# Scarab.net
KiCad netlist of a schematic drawn in EAGLE
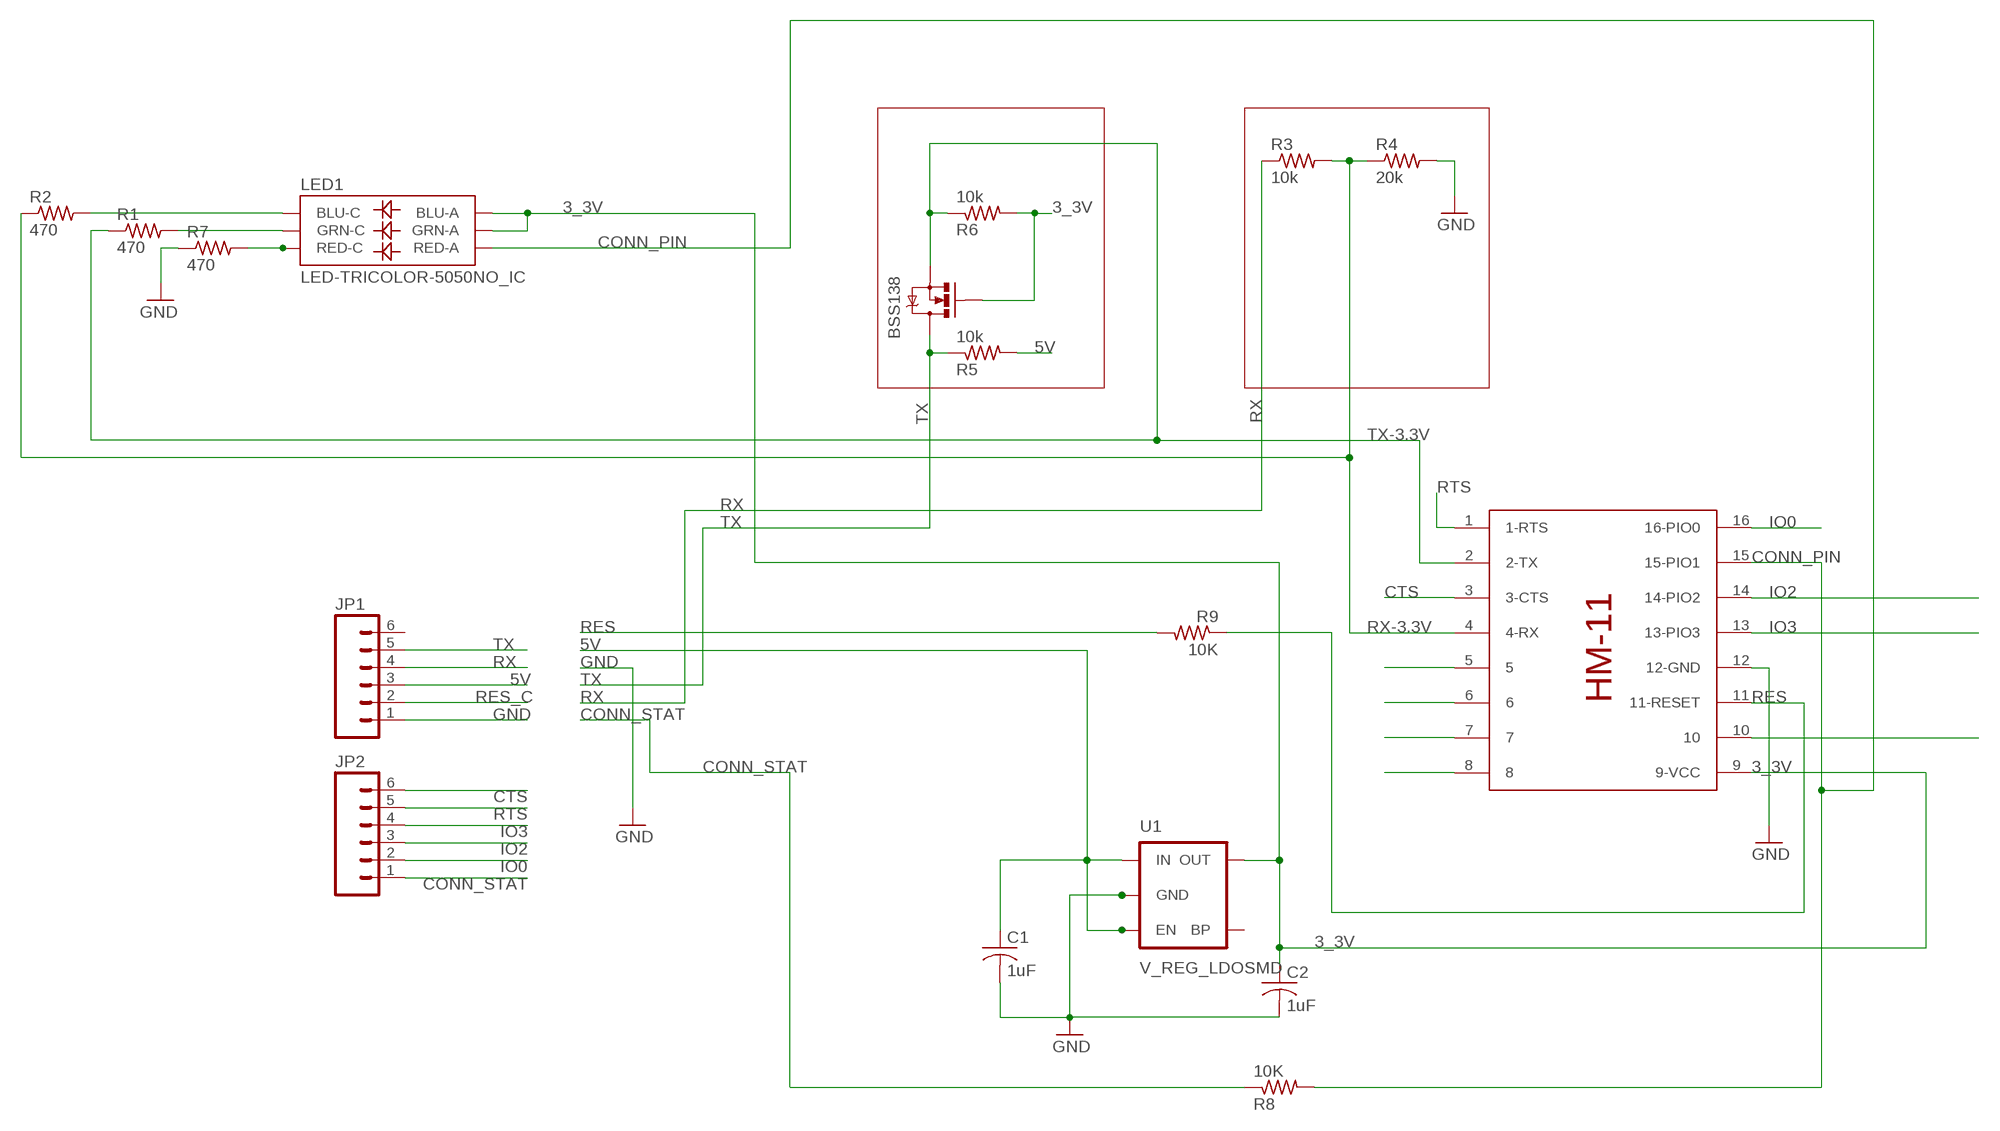
[diagram p0: schematic, sheet 1]

(export (version "E")
  (design (tool "Eeschema 10.0.6"))
  (components
    (comp (ref "BSS138")
      (value "MOSFET-NCHANNELSMD")
      (footprint "eagle-import:SOT23-3")
      (libsource (lib "eagle-import") (part "MOSFET-NCHANNELSMD"))
    )
    (comp (ref "C1")
      (value "1uF")
      (footprint "eagle-import:C0402")
      (libsource (lib "eagle-import") (part "C-USC0402"))
    )
    (comp (ref "C2")
      (value "1uF")
      (footprint "eagle-import:C0402")
      (libsource (lib "eagle-import") (part "C-USC0402"))
    )
    (comp (ref "JP1")
      (value "M06LOCK")
      (footprint "eagle-import:1X06_LOCK")
      (libsource (lib "eagle-import") (part "M06LOCK"))
    )
    (comp (ref "JP2")
      (value "M06LOCK")
      (footprint "eagle-import:1X06_LOCK")
      (libsource (lib "eagle-import") (part "M06LOCK"))
    )
    (comp (ref "LED1")
      (value "LED-TRICOLOR-5050NO_IC")
      (footprint "eagle-import:LED-TRICOLOR-5050")
      (libsource (lib "eagle-import") (part "LED-TRICOLOR-5050NO_IC"))
    )
    (comp (ref "R1")
      (value "470")
      (footprint "eagle-import:R0402")
      (libsource (lib "eagle-import") (part "R-US_R0402"))
    )
    (comp (ref "R2")
      (value "470")
      (footprint "eagle-import:R0402")
      (libsource (lib "eagle-import") (part "R-US_R0402"))
    )
    (comp (ref "R3")
      (value "10k")
      (footprint "eagle-import:R0402")
      (libsource (lib "eagle-import") (part "R-US_R0402"))
    )
    (comp (ref "R4")
      (value "20k")
      (footprint "eagle-import:R0402")
      (libsource (lib "eagle-import") (part "R-US_R0402"))
    )
    (comp (ref "R5")
      (value "10k")
      (footprint "eagle-import:R0402")
      (libsource (lib "eagle-import") (part "R-US_R0402"))
    )
    (comp (ref "R6")
      (value "10k")
      (footprint "eagle-import:R0402")
      (libsource (lib "eagle-import") (part "R-US_R0402"))
    )
    (comp (ref "R7")
      (value "470")
      (footprint "eagle-import:R0402")
      (libsource (lib "eagle-import") (part "R-US_R0402"))
    )
    (comp (ref "R8")
      (value "10K")
      (footprint "eagle-import:R0402")
      (libsource (lib "eagle-import") (part "R-US_R0402"))
    )
    (comp (ref "R9")
      (value "10K")
      (footprint "eagle-import:R0402")
      (libsource (lib "eagle-import") (part "R-US_R0402"))
    )
    (comp (ref "U$1")
      (value "HM-11")
      (footprint "eagle-import:HM-11")
      (libsource (lib "eagle-import") (part "HM-11"))
    )
    (comp (ref "U1")
      (value "V_REG_LDOSMD")
      (footprint "eagle-import:SOT23-5")
      (libsource (lib "eagle-import") (part "V_REG_LDOSMD"))
    )
  )
  (nets
    (net (code "1") (name "/3_3V") (class "Default")
      (node (ref "BSS138") (pin "1") (pinfunction "G_1") (pintype "passive"))
      (node (ref "C2") (pin "1") (pinfunction "1_1") (pintype "passive"))
      (node (ref "LED1") (pin "1") (pinfunction "GRN-A_1") (pintype "bidirectional"))
      (node (ref "LED1") (pin "3") (pinfunction "BLU-A_3") (pintype "bidirectional"))
      (node (ref "R6") (pin "2") (pinfunction "2_2") (pintype "passive"))
      (node (ref "U$1") (pin "9") (pinfunction "9-VCC_9") (pintype "bidirectional"))
      (node (ref "U1") (pin "5") (pinfunction "OUT_5") (pintype "passive"))
    )
    (net (code "2") (name "/5V") (class "Default")
      (node (ref "C1") (pin "1") (pinfunction "1_1") (pintype "passive"))
      (node (ref "JP1") (pin "3") (pinfunction "3_3") (pintype "passive"))
      (node (ref "R5") (pin "2") (pinfunction "2_2") (pintype "passive"))
      (node (ref "U1") (pin "1") (pinfunction "IN_1") (pintype "input"))
      (node (ref "U1") (pin "3") (pinfunction "EN_3") (pintype "input"))
    )
    (net (code "3") (name "/CONN_PIN") (class "Default")
      (node (ref "LED1") (pin "2") (pinfunction "RED-A_2") (pintype "bidirectional"))
      (node (ref "R8") (pin "2") (pinfunction "2_2") (pintype "passive"))
      (node (ref "U$1") (pin "15") (pinfunction "15-PIO1_15") (pintype "bidirectional"))
    )
    (net (code "4") (name "/CONN_STAT") (class "Default")
      (node (ref "JP2") (pin "1") (pinfunction "1_1") (pintype "passive"))
      (node (ref "R8") (pin "1") (pinfunction "1_1") (pintype "passive"))
    )
    (net (code "5") (name "/CTS") (class "Default")
      (node (ref "JP2") (pin "6") (pinfunction "6_6") (pintype "passive"))
      (node (ref "U$1") (pin "3") (pinfunction "3-CTS_3") (pintype "bidirectional"))
    )
    (net (code "6") (name "/IO0") (class "Default")
      (node (ref "JP2") (pin "2") (pinfunction "2_2") (pintype "passive"))
      (node (ref "U$1") (pin "16") (pinfunction "16-PIO0_16") (pintype "bidirectional"))
    )
    (net (code "7") (name "/IO2") (class "Default")
      (node (ref "JP2") (pin "3") (pinfunction "3_3") (pintype "passive"))
      (node (ref "U$1") (pin "14") (pinfunction "14-PIO2_14") (pintype "bidirectional"))
    )
    (net (code "8") (name "/IO3") (class "Default")
      (node (ref "JP2") (pin "4") (pinfunction "4_4") (pintype "passive"))
      (node (ref "U$1") (pin "13") (pinfunction "13-PIO3_13") (pintype "bidirectional"))
    )
    (net (code "9") (name "/RES") (class "Default")
      (node (ref "R9") (pin "1") (pinfunction "1_1") (pintype "passive"))
      (node (ref "U$1") (pin "11") (pinfunction "11-RESET_11") (pintype "bidirectional"))
    )
    (net (code "10") (name "/RES_C") (class "Default")
      (node (ref "JP1") (pin "2") (pinfunction "2_2") (pintype "passive"))
      (node (ref "R9") (pin "2") (pinfunction "2_2") (pintype "passive"))
    )
    (net (code "11") (name "/RTS") (class "Default")
      (node (ref "JP2") (pin "5") (pinfunction "5_5") (pintype "passive"))
      (node (ref "U$1") (pin "1") (pinfunction "1-RTS_1") (pintype "bidirectional"))
    )
    (net (code "12") (name "/RX") (class "Default")
      (node (ref "JP1") (pin "4") (pinfunction "4_4") (pintype "passive"))
      (node (ref "R3") (pin "1") (pinfunction "1_1") (pintype "passive"))
    )
    (net (code "13") (name "/RX-3.3V") (class "Default")
      (node (ref "R2") (pin "1") (pinfunction "1_1") (pintype "passive"))
      (node (ref "R3") (pin "2") (pinfunction "2_2") (pintype "passive"))
      (node (ref "R4") (pin "1") (pinfunction "1_1") (pintype "passive"))
      (node (ref "U$1") (pin "4") (pinfunction "4-RX_4") (pintype "bidirectional"))
    )
    (net (code "14") (name "/TX") (class "Default")
      (node (ref "BSS138") (pin "3") (pinfunction "D_3") (pintype "passive"))
      (node (ref "JP1") (pin "5") (pinfunction "5_5") (pintype "passive"))
      (node (ref "R5") (pin "1") (pinfunction "1_1") (pintype "passive"))
    )
    (net (code "15") (name "/TX-3.3V") (class "Default")
      (node (ref "BSS138") (pin "2") (pinfunction "S_2") (pintype "passive"))
      (node (ref "R1") (pin "1") (pinfunction "1_1") (pintype "passive"))
      (node (ref "R6") (pin "1") (pinfunction "1_1") (pintype "passive"))
      (node (ref "U$1") (pin "2") (pinfunction "2-TX_2") (pintype "bidirectional"))
    )
    (net (code "16") (name "GND") (class "Default")
      (node (ref "C1") (pin "2") (pinfunction "2_2") (pintype "passive"))
      (node (ref "C2") (pin "2") (pinfunction "2_2") (pintype "passive"))
      (node (ref "JP1") (pin "1") (pinfunction "1_1") (pintype "passive"))
      (node (ref "R4") (pin "2") (pinfunction "2_2") (pintype "passive"))
      (node (ref "R7") (pin "1") (pinfunction "1_1") (pintype "passive"))
      (node (ref "U$1") (pin "12") (pinfunction "12-GND_12") (pintype "bidirectional"))
      (node (ref "U1") (pin "2") (pinfunction "GND_2") (pintype "input"))
    )
    (net (code "17") (name "Net-(LED1-BLU-C)") (class "Default")
      (node (ref "LED1") (pin "4") (pinfunction "BLU-C_4") (pintype "bidirectional"))
      (node (ref "R2") (pin "2") (pinfunction "2_2") (pintype "passive"))
    )
    (net (code "18") (name "Net-(LED1-GRN-C)") (class "Default")
      (node (ref "LED1") (pin "6") (pinfunction "GRN-C_6") (pintype "bidirectional"))
      (node (ref "R1") (pin "2") (pinfunction "2_2") (pintype "passive"))
    )
    (net (code "19") (name "Net-(LED1-RED-C)") (class "Default")
      (node (ref "LED1") (pin "5") (pinfunction "RED-C_5") (pintype "bidirectional"))
      (node (ref "R7") (pin "2") (pinfunction "2_2") (pintype "passive"))
    )
    (net (code "20") (name "unconnected-(JP1-Pad6)") (class "Default")
      (node (ref "JP1") (pin "6") (pinfunction "6_6") (pintype "passive"))
    )
    (net (code "21") (name "unconnected-(U$1-Pad5)") (class "Default")
      (node (ref "U$1") (pin "5") (pinfunction "5_5") (pintype "bidirectional"))
    )
    (net (code "22") (name "unconnected-(U$1-Pad6)") (class "Default")
      (node (ref "U$1") (pin "6") (pinfunction "6_6") (pintype "bidirectional"))
    )
    (net (code "23") (name "unconnected-(U$1-Pad7)") (class "Default")
      (node (ref "U$1") (pin "7") (pinfunction "7_7") (pintype "bidirectional"))
    )
    (net (code "24") (name "unconnected-(U$1-Pad8)") (class "Default")
      (node (ref "U$1") (pin "8") (pinfunction "8_8") (pintype "bidirectional"))
    )
    (net (code "25") (name "unconnected-(U$1-Pad10)") (class "Default")
      (node (ref "U$1") (pin "10") (pinfunction "10_10") (pintype "bidirectional"))
    )
    (net (code "26") (name "unconnected-(U1-BP-Pad4)") (class "Default")
      (node (ref "U1") (pin "4") (pinfunction "BP_4") (pintype "input"))
    )
  )
)
